# BluetoothBoard.net
KiCad netlist of a schematic drawn in EAGLE
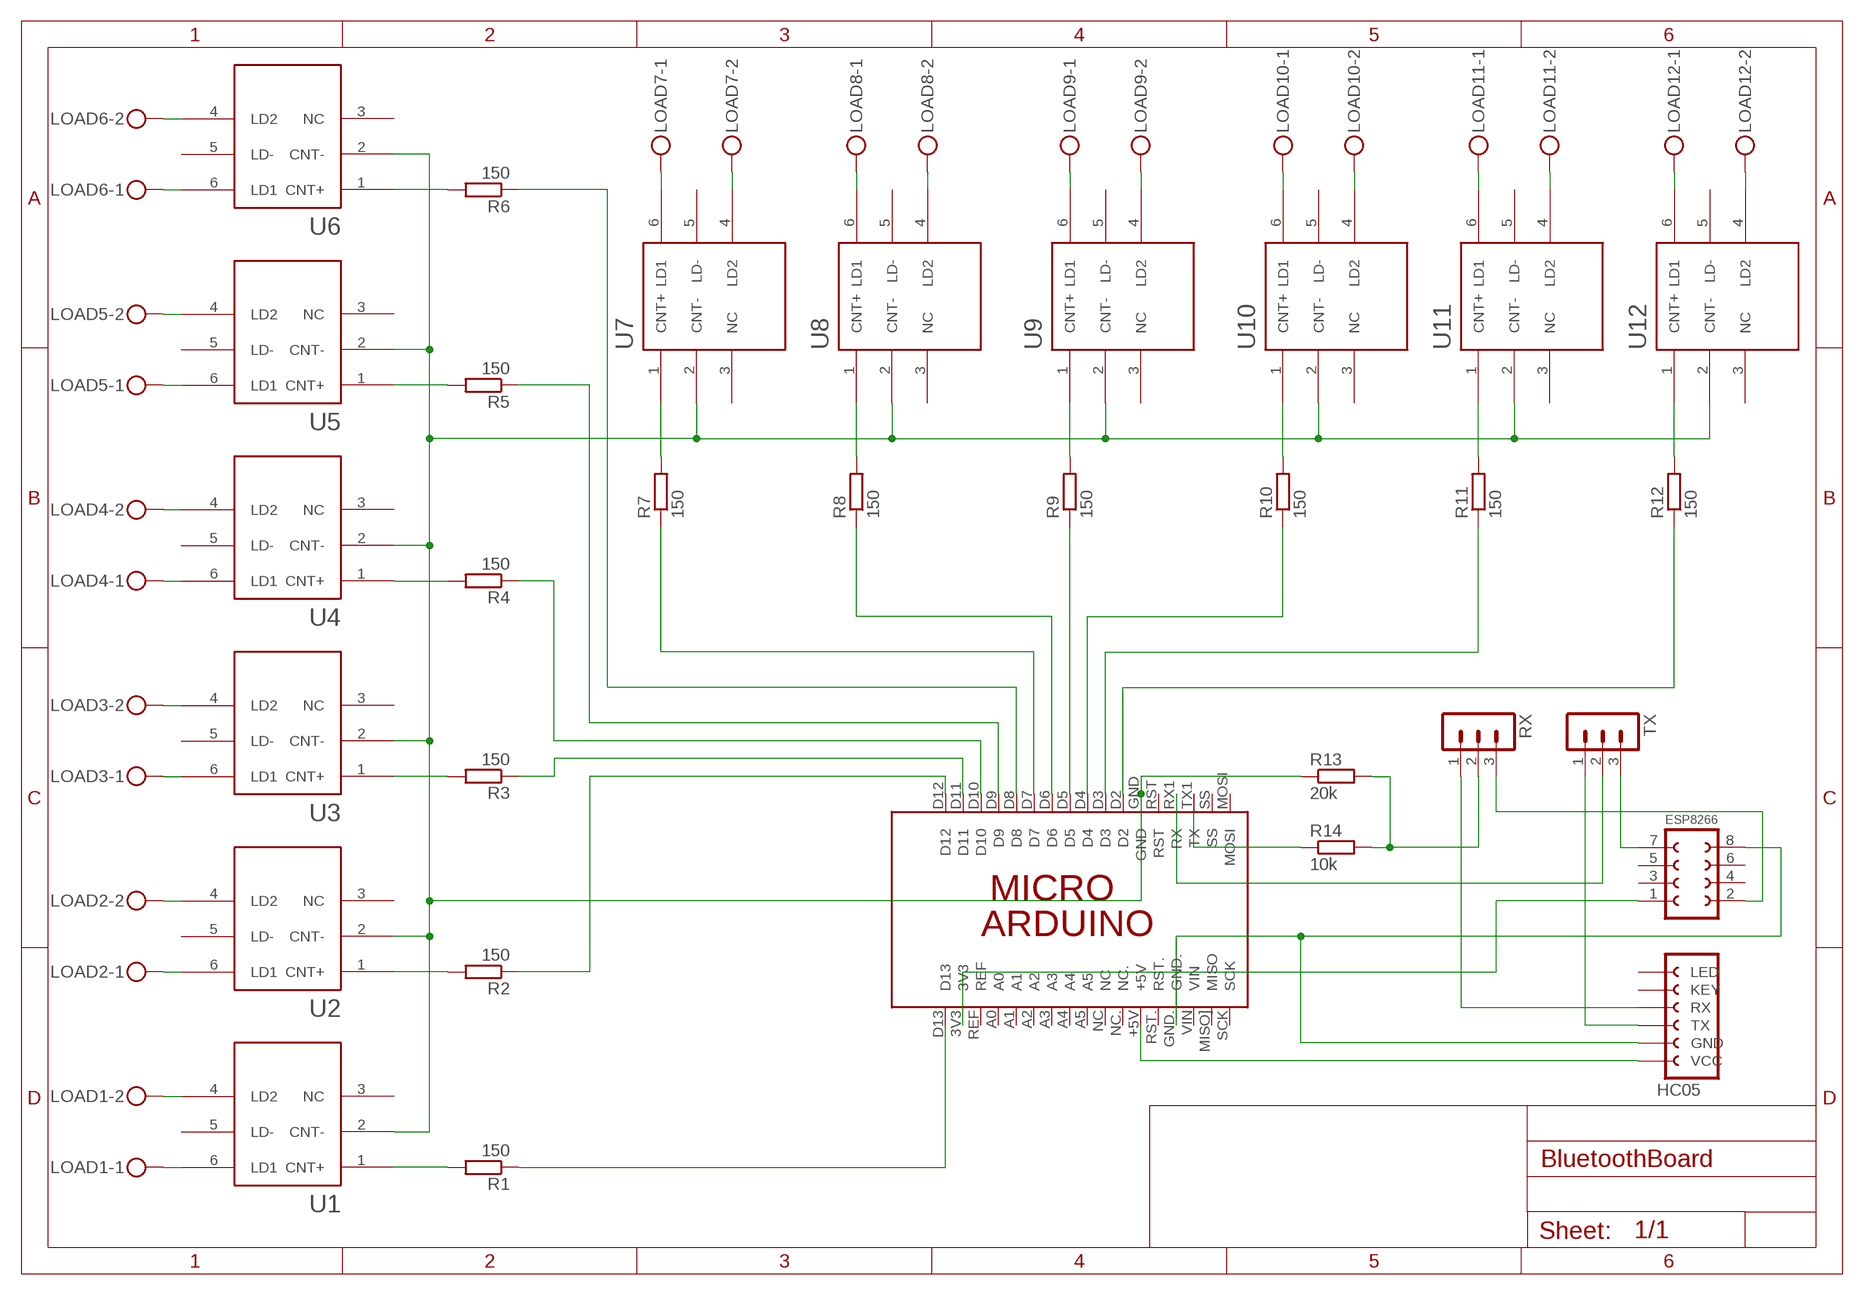
[diagram p0: schematic, sheet 1]

(export (version "E")
  (design (tool "Eeschema 10.0.6"))
  (components
    (comp (ref "ESP8266")
      (value "ESP8266")
      (footprint "eagle-import:ESP8266")
      (libsource (lib "eagle-import") (part "ESP8266"))
    )
    (comp (ref "HC05")
      (value "FE06-1")
      (footprint "eagle-import:FE06")
      (libsource (lib "eagle-import") (part "FE06-1"))
    )
    (comp (ref "LOAD1")
      (value "MKDSN1,5/2-5,08")
      (footprint "eagle-import:MKDSN1,5_2-5,08")
      (libsource (lib "eagle-import") (part "MKDSN1,5/2-5,08"))
    )
    (comp (ref "LOAD2")
      (value "MKDSN1,5/2-5,08")
      (footprint "eagle-import:MKDSN1,5_2-5,08")
      (libsource (lib "eagle-import") (part "MKDSN1,5/2-5,08"))
    )
    (comp (ref "LOAD3")
      (value "MKDSN1,5/2-5,08")
      (footprint "eagle-import:MKDSN1,5_2-5,08")
      (libsource (lib "eagle-import") (part "MKDSN1,5/2-5,08"))
    )
    (comp (ref "LOAD4")
      (value "MKDSN1,5/2-5,08")
      (footprint "eagle-import:MKDSN1,5_2-5,08")
      (libsource (lib "eagle-import") (part "MKDSN1,5/2-5,08"))
    )
    (comp (ref "LOAD5")
      (value "MKDSN1,5/2-5,08")
      (footprint "eagle-import:MKDSN1,5_2-5,08")
      (libsource (lib "eagle-import") (part "MKDSN1,5/2-5,08"))
    )
    (comp (ref "LOAD6")
      (value "MKDSN1,5/2-5,08")
      (footprint "eagle-import:MKDSN1,5_2-5,08")
      (libsource (lib "eagle-import") (part "MKDSN1,5/2-5,08"))
    )
    (comp (ref "LOAD7")
      (value "MKDSN1,5/2-5,08")
      (footprint "eagle-import:MKDSN1,5_2-5,08")
      (libsource (lib "eagle-import") (part "MKDSN1,5/2-5,08"))
    )
    (comp (ref "LOAD8")
      (value "MKDSN1,5/2-5,08")
      (footprint "eagle-import:MKDSN1,5_2-5,08")
      (libsource (lib "eagle-import") (part "MKDSN1,5/2-5,08"))
    )
    (comp (ref "LOAD9")
      (value "MKDSN1,5/2-5,08")
      (footprint "eagle-import:MKDSN1,5_2-5,08")
      (libsource (lib "eagle-import") (part "MKDSN1,5/2-5,08"))
    )
    (comp (ref "LOAD10")
      (value "MKDSN1,5/2-5,08")
      (footprint "eagle-import:MKDSN1,5_2-5,08")
      (libsource (lib "eagle-import") (part "MKDSN1,5/2-5,08"))
    )
    (comp (ref "LOAD11")
      (value "MKDSN1,5/2-5,08")
      (footprint "eagle-import:MKDSN1,5_2-5,08")
      (libsource (lib "eagle-import") (part "MKDSN1,5/2-5,08"))
    )
    (comp (ref "LOAD12")
      (value "MKDSN1,5/2-5,08")
      (footprint "eagle-import:MKDSN1,5_2-5,08")
      (libsource (lib "eagle-import") (part "MKDSN1,5/2-5,08"))
    )
    (comp (ref "R1")
      (value "150")
      (footprint "eagle-import:0207_7")
      (libsource (lib "eagle-import") (part "R-EU_0207/7"))
    )
    (comp (ref "R2")
      (value "150")
      (footprint "eagle-import:0207_7")
      (libsource (lib "eagle-import") (part "R-EU_0207/7"))
    )
    (comp (ref "R3")
      (value "150")
      (footprint "eagle-import:0207_7")
      (libsource (lib "eagle-import") (part "R-EU_0207/7"))
    )
    (comp (ref "R4")
      (value "150")
      (footprint "eagle-import:0207_7")
      (libsource (lib "eagle-import") (part "R-EU_0207/7"))
    )
    (comp (ref "R5")
      (value "150")
      (footprint "eagle-import:0207_7")
      (libsource (lib "eagle-import") (part "R-EU_0207/7"))
    )
    (comp (ref "R6")
      (value "150")
      (footprint "eagle-import:0207_7")
      (libsource (lib "eagle-import") (part "R-EU_0207/7"))
    )
    (comp (ref "R7")
      (value "150")
      (footprint "eagle-import:0207_7")
      (libsource (lib "eagle-import") (part "R-EU_0207/7"))
    )
    (comp (ref "R8")
      (value "150")
      (footprint "eagle-import:0207_7")
      (libsource (lib "eagle-import") (part "R-EU_0207/7"))
    )
    (comp (ref "R9")
      (value "150")
      (footprint "eagle-import:0207_7")
      (libsource (lib "eagle-import") (part "R-EU_0207/7"))
    )
    (comp (ref "R10")
      (value "150")
      (footprint "eagle-import:0207_7")
      (libsource (lib "eagle-import") (part "R-EU_0207/7"))
    )
    (comp (ref "R11")
      (value "150")
      (footprint "eagle-import:0207_7")
      (libsource (lib "eagle-import") (part "R-EU_0207/7"))
    )
    (comp (ref "R12")
      (value "150")
      (footprint "eagle-import:0207_7")
      (libsource (lib "eagle-import") (part "R-EU_0207/7"))
    )
    (comp (ref "R13")
      (value "20k")
      (footprint "eagle-import:0207_7")
      (libsource (lib "eagle-import") (part "R-EU_0207/7"))
    )
    (comp (ref "R14")
      (value "10k")
      (footprint "eagle-import:0207_7")
      (libsource (lib "eagle-import") (part "R-EU_0207/7"))
    )
    (comp (ref "RX")
      (value "MA03-1")
      (footprint "eagle-import:MA03-1")
      (libsource (lib "eagle-import") (part "MA03-1"))
    )
    (comp (ref "TX")
      (value "MA03-1")
      (footprint "eagle-import:MA03-1")
      (libsource (lib "eagle-import") (part "MA03-1"))
    )
    (comp (ref "U1")
      (value "LCA710")
      (footprint "eagle-import:DIL-06")
      (libsource (lib "eagle-import") (part "LCA710"))
    )
    (comp (ref "U2")
      (value "LCA710")
      (footprint "eagle-import:DIL-06")
      (libsource (lib "eagle-import") (part "LCA710"))
    )
    (comp (ref "U3")
      (value "LCA710")
      (footprint "eagle-import:DIL-06")
      (libsource (lib "eagle-import") (part "LCA710"))
    )
    (comp (ref "U4")
      (value "LCA710")
      (footprint "eagle-import:DIL-06")
      (libsource (lib "eagle-import") (part "LCA710"))
    )
    (comp (ref "U5")
      (value "LCA710")
      (footprint "eagle-import:DIL-06")
      (libsource (lib "eagle-import") (part "LCA710"))
    )
    (comp (ref "U6")
      (value "LCA710")
      (footprint "eagle-import:DIL-06")
      (libsource (lib "eagle-import") (part "LCA710"))
    )
    (comp (ref "U7")
      (value "LCA710")
      (footprint "eagle-import:DIL-06")
      (libsource (lib "eagle-import") (part "LCA710"))
    )
    (comp (ref "U8")
      (value "LCA710")
      (footprint "eagle-import:DIL-06")
      (libsource (lib "eagle-import") (part "LCA710"))
    )
    (comp (ref "U9")
      (value "LCA710")
      (footprint "eagle-import:DIL-06")
      (libsource (lib "eagle-import") (part "LCA710"))
    )
    (comp (ref "U10")
      (value "LCA710")
      (footprint "eagle-import:DIL-06")
      (libsource (lib "eagle-import") (part "LCA710"))
    )
    (comp (ref "U11")
      (value "LCA710")
      (footprint "eagle-import:DIL-06")
      (libsource (lib "eagle-import") (part "LCA710"))
    )
    (comp (ref "U12")
      (value "LCA710")
      (footprint "eagle-import:DIL-06")
      (libsource (lib "eagle-import") (part "LCA710"))
    )
    (comp (ref "UC")
      (value "ARDUINO_MICRO")
      (footprint "eagle-import:ARDUINO_MICRO")
      (libsource (lib "eagle-import") (part "ARDUINO_MICRO"))
    )
  )
  (nets
    (net (code "1") (name "Net-(ESP8266-Pad1)") (class "Default")
      (node (ref "ESP8266") (pin "1") (pinfunction "1_1") (pintype "passive"))
      (node (ref "UC") (pin "3V3") (pinfunction "3V3_3V3") (pintype "bidirectional"))
    )
    (net (code "2") (name "Net-(ESP8266-Pad2)") (class "Default")
      (node (ref "ESP8266") (pin "2") (pinfunction "2_2") (pintype "passive"))
      (node (ref "RX") (pin "3") (pinfunction "3_3") (pintype "passive"))
    )
    (net (code "3") (name "Net-(ESP8266-TX)") (class "Default")
      (node (ref "ESP8266") (pin "7") (pinfunction "TX_7") (pintype "passive"))
      (node (ref "TX") (pin "3") (pinfunction "3_3") (pintype "passive"))
    )
    (net (code "4") (name "Net-(HC05-GND)") (class "Default")
      (node (ref "ESP8266") (pin "8") (pinfunction "8_8") (pintype "passive"))
      (node (ref "HC05") (pin "5") (pinfunction "GND_5") (pintype "passive"))
      (node (ref "UC") (pin "GND.") (pinfunction "GND._GND.") (pintype "bidirectional"))
    )
    (net (code "5") (name "Net-(HC05-RX)") (class "Default")
      (node (ref "HC05") (pin "3") (pinfunction "RX_3") (pintype "passive"))
      (node (ref "RX") (pin "1") (pinfunction "1_1") (pintype "passive"))
    )
    (net (code "6") (name "Net-(HC05-TX)") (class "Default")
      (node (ref "HC05") (pin "4") (pinfunction "TX_4") (pintype "passive"))
      (node (ref "TX") (pin "1") (pinfunction "1_1") (pintype "passive"))
    )
    (net (code "7") (name "Net-(HC05-VCC)") (class "Default")
      (node (ref "HC05") (pin "6") (pinfunction "VCC_6") (pintype "passive"))
      (node (ref "UC") (pin "+5V") (pinfunction "+5V_+5V") (pintype "bidirectional"))
    )
    (net (code "8") (name "Net-(LOAD1A-KL)") (class "Default")
      (node (ref "LOAD1") (pin "1") (pinfunction "KL_1") (pintype "passive"))
      (node (ref "U1") (pin "6") (pinfunction "LD1_6") (pintype "passive"))
    )
    (net (code "9") (name "Net-(LOAD1B-KL)") (class "Default")
      (node (ref "LOAD1") (pin "2") (pinfunction "KL_2") (pintype "passive"))
      (node (ref "U1") (pin "4") (pinfunction "LD2_4") (pintype "passive"))
    )
    (net (code "10") (name "Net-(LOAD2A-KL)") (class "Default")
      (node (ref "LOAD2") (pin "1") (pinfunction "KL_1") (pintype "passive"))
      (node (ref "U2") (pin "6") (pinfunction "LD1_6") (pintype "passive"))
    )
    (net (code "11") (name "Net-(LOAD2B-KL)") (class "Default")
      (node (ref "LOAD2") (pin "2") (pinfunction "KL_2") (pintype "passive"))
      (node (ref "U2") (pin "4") (pinfunction "LD2_4") (pintype "passive"))
    )
    (net (code "12") (name "Net-(LOAD3A-KL)") (class "Default")
      (node (ref "LOAD3") (pin "1") (pinfunction "KL_1") (pintype "passive"))
      (node (ref "U3") (pin "6") (pinfunction "LD1_6") (pintype "passive"))
    )
    (net (code "13") (name "Net-(LOAD3B-KL)") (class "Default")
      (node (ref "LOAD3") (pin "2") (pinfunction "KL_2") (pintype "passive"))
      (node (ref "U3") (pin "4") (pinfunction "LD2_4") (pintype "passive"))
    )
    (net (code "14") (name "Net-(LOAD4A-KL)") (class "Default")
      (node (ref "LOAD4") (pin "1") (pinfunction "KL_1") (pintype "passive"))
      (node (ref "U4") (pin "6") (pinfunction "LD1_6") (pintype "passive"))
    )
    (net (code "15") (name "Net-(LOAD4B-KL)") (class "Default")
      (node (ref "LOAD4") (pin "2") (pinfunction "KL_2") (pintype "passive"))
      (node (ref "U4") (pin "4") (pinfunction "LD2_4") (pintype "passive"))
    )
    (net (code "16") (name "Net-(LOAD5A-KL)") (class "Default")
      (node (ref "LOAD5") (pin "1") (pinfunction "KL_1") (pintype "passive"))
      (node (ref "U5") (pin "6") (pinfunction "LD1_6") (pintype "passive"))
    )
    (net (code "17") (name "Net-(LOAD5B-KL)") (class "Default")
      (node (ref "LOAD5") (pin "2") (pinfunction "KL_2") (pintype "passive"))
      (node (ref "U5") (pin "4") (pinfunction "LD2_4") (pintype "passive"))
    )
    (net (code "18") (name "Net-(LOAD6A-KL)") (class "Default")
      (node (ref "LOAD6") (pin "1") (pinfunction "KL_1") (pintype "passive"))
      (node (ref "U6") (pin "6") (pinfunction "LD1_6") (pintype "passive"))
    )
    (net (code "19") (name "Net-(LOAD6B-KL)") (class "Default")
      (node (ref "LOAD6") (pin "2") (pinfunction "KL_2") (pintype "passive"))
      (node (ref "U6") (pin "4") (pinfunction "LD2_4") (pintype "passive"))
    )
    (net (code "20") (name "Net-(LOAD7A-KL)") (class "Default")
      (node (ref "LOAD7") (pin "1") (pinfunction "KL_1") (pintype "passive"))
      (node (ref "U7") (pin "6") (pinfunction "LD1_6") (pintype "passive"))
    )
    (net (code "21") (name "Net-(LOAD7B-KL)") (class "Default")
      (node (ref "LOAD7") (pin "2") (pinfunction "KL_2") (pintype "passive"))
      (node (ref "U7") (pin "4") (pinfunction "LD2_4") (pintype "passive"))
    )
    (net (code "22") (name "Net-(LOAD8A-KL)") (class "Default")
      (node (ref "LOAD8") (pin "1") (pinfunction "KL_1") (pintype "passive"))
      (node (ref "U8") (pin "6") (pinfunction "LD1_6") (pintype "passive"))
    )
    (net (code "23") (name "Net-(LOAD8B-KL)") (class "Default")
      (node (ref "LOAD8") (pin "2") (pinfunction "KL_2") (pintype "passive"))
      (node (ref "U8") (pin "4") (pinfunction "LD2_4") (pintype "passive"))
    )
    (net (code "24") (name "Net-(LOAD9A-KL)") (class "Default")
      (node (ref "LOAD9") (pin "1") (pinfunction "KL_1") (pintype "passive"))
      (node (ref "U9") (pin "6") (pinfunction "LD1_6") (pintype "passive"))
    )
    (net (code "25") (name "Net-(LOAD9B-KL)") (class "Default")
      (node (ref "LOAD9") (pin "2") (pinfunction "KL_2") (pintype "passive"))
      (node (ref "U9") (pin "4") (pinfunction "LD2_4") (pintype "passive"))
    )
    (net (code "26") (name "Net-(LOAD10A-KL)") (class "Default")
      (node (ref "LOAD10") (pin "1") (pinfunction "KL_1") (pintype "passive"))
      (node (ref "U10") (pin "6") (pinfunction "LD1_6") (pintype "passive"))
    )
    (net (code "27") (name "Net-(LOAD10B-KL)") (class "Default")
      (node (ref "LOAD10") (pin "2") (pinfunction "KL_2") (pintype "passive"))
      (node (ref "U10") (pin "4") (pinfunction "LD2_4") (pintype "passive"))
    )
    (net (code "28") (name "Net-(LOAD11A-KL)") (class "Default")
      (node (ref "LOAD11") (pin "1") (pinfunction "KL_1") (pintype "passive"))
      (node (ref "U11") (pin "6") (pinfunction "LD1_6") (pintype "passive"))
    )
    (net (code "29") (name "Net-(LOAD11B-KL)") (class "Default")
      (node (ref "LOAD11") (pin "2") (pinfunction "KL_2") (pintype "passive"))
      (node (ref "U11") (pin "4") (pinfunction "LD2_4") (pintype "passive"))
    )
    (net (code "30") (name "Net-(LOAD12A-KL)") (class "Default")
      (node (ref "LOAD12") (pin "1") (pinfunction "KL_1") (pintype "passive"))
      (node (ref "U12") (pin "6") (pinfunction "LD1_6") (pintype "passive"))
    )
    (net (code "31") (name "Net-(LOAD12B-KL)") (class "Default")
      (node (ref "LOAD12") (pin "2") (pinfunction "KL_2") (pintype "passive"))
      (node (ref "U12") (pin "4") (pinfunction "LD2_4") (pintype "passive"))
    )
    (net (code "32") (name "Net-(R1-Pad1)") (class "Default")
      (node (ref "R1") (pin "1") (pinfunction "1_1") (pintype "passive"))
      (node (ref "UC") (pin "D13") (pinfunction "D13_D13") (pintype "bidirectional"))
    )
    (net (code "33") (name "Net-(R2-Pad1)") (class "Default")
      (node (ref "R2") (pin "1") (pinfunction "1_1") (pintype "passive"))
      (node (ref "UC") (pin "D12") (pinfunction "D12_D12") (pintype "bidirectional"))
    )
    (net (code "34") (name "Net-(R3-Pad1)") (class "Default")
      (node (ref "R3") (pin "1") (pinfunction "1_1") (pintype "passive"))
      (node (ref "UC") (pin "D11") (pinfunction "D11_D11") (pintype "bidirectional"))
    )
    (net (code "35") (name "Net-(R4-Pad1)") (class "Default")
      (node (ref "R4") (pin "1") (pinfunction "1_1") (pintype "passive"))
      (node (ref "UC") (pin "D10") (pinfunction "D10_D10") (pintype "bidirectional"))
    )
    (net (code "36") (name "Net-(R5-Pad1)") (class "Default")
      (node (ref "R5") (pin "1") (pinfunction "1_1") (pintype "passive"))
      (node (ref "UC") (pin "D9") (pinfunction "D9_D9") (pintype "bidirectional"))
    )
    (net (code "37") (name "Net-(R6-Pad1)") (class "Default")
      (node (ref "R6") (pin "1") (pinfunction "1_1") (pintype "passive"))
      (node (ref "UC") (pin "D8") (pinfunction "D8_D8") (pintype "bidirectional"))
    )
    (net (code "38") (name "Net-(R7-Pad1)") (class "Default")
      (node (ref "R7") (pin "1") (pinfunction "1_1") (pintype "passive"))
      (node (ref "UC") (pin "D7") (pinfunction "D7_D7") (pintype "bidirectional"))
    )
    (net (code "39") (name "Net-(R8-Pad1)") (class "Default")
      (node (ref "R8") (pin "1") (pinfunction "1_1") (pintype "passive"))
      (node (ref "UC") (pin "D6") (pinfunction "D6_D6") (pintype "bidirectional"))
    )
    (net (code "40") (name "Net-(R9-Pad1)") (class "Default")
      (node (ref "R9") (pin "1") (pinfunction "1_1") (pintype "passive"))
      (node (ref "UC") (pin "D5") (pinfunction "D5_D5") (pintype "bidirectional"))
    )
    (net (code "41") (name "Net-(R10-Pad1)") (class "Default")
      (node (ref "R10") (pin "1") (pinfunction "1_1") (pintype "passive"))
      (node (ref "UC") (pin "D4") (pinfunction "D4_D4") (pintype "bidirectional"))
    )
    (net (code "42") (name "Net-(R11-Pad1)") (class "Default")
      (node (ref "R11") (pin "1") (pinfunction "1_1") (pintype "passive"))
      (node (ref "UC") (pin "D3") (pinfunction "D3_D3") (pintype "bidirectional"))
    )
    (net (code "43") (name "Net-(R12-Pad1)") (class "Default")
      (node (ref "R12") (pin "1") (pinfunction "1_1") (pintype "passive"))
      (node (ref "UC") (pin "D2") (pinfunction "D2_D2") (pintype "bidirectional"))
    )
    (net (code "44") (name "Net-(R13-Pad2)") (class "Default")
      (node (ref "R13") (pin "2") (pinfunction "2_2") (pintype "passive"))
      (node (ref "R14") (pin "2") (pinfunction "2_2") (pintype "passive"))
      (node (ref "RX") (pin "2") (pinfunction "2_2") (pintype "passive"))
    )
    (net (code "45") (name "Net-(U1-CNT+)") (class "Default")
      (node (ref "R1") (pin "2") (pinfunction "2_2") (pintype "passive"))
      (node (ref "U1") (pin "1") (pinfunction "CNT+_1") (pintype "passive"))
    )
    (net (code "46") (name "Net-(U1-CNT-)") (class "Default")
      (node (ref "R13") (pin "1") (pinfunction "1_1") (pintype "passive"))
      (node (ref "U1") (pin "2") (pinfunction "CNT-_2") (pintype "passive"))
      (node (ref "U10") (pin "2") (pinfunction "CNT-_2") (pintype "passive"))
      (node (ref "U11") (pin "2") (pinfunction "CNT-_2") (pintype "passive"))
      (node (ref "U12") (pin "2") (pinfunction "CNT-_2") (pintype "passive"))
      (node (ref "U2") (pin "2") (pinfunction "CNT-_2") (pintype "passive"))
      (node (ref "U3") (pin "2") (pinfunction "CNT-_2") (pintype "passive"))
      (node (ref "U4") (pin "2") (pinfunction "CNT-_2") (pintype "passive"))
      (node (ref "U5") (pin "2") (pinfunction "CNT-_2") (pintype "passive"))
      (node (ref "U6") (pin "2") (pinfunction "CNT-_2") (pintype "passive"))
      (node (ref "U7") (pin "2") (pinfunction "CNT-_2") (pintype "passive"))
      (node (ref "U8") (pin "2") (pinfunction "CNT-_2") (pintype "passive"))
      (node (ref "U9") (pin "2") (pinfunction "CNT-_2") (pintype "passive"))
      (node (ref "UC") (pin "GND") (pinfunction "GND_GND") (pintype "bidirectional"))
    )
    (net (code "47") (name "Net-(U2-CNT+)") (class "Default")
      (node (ref "R2") (pin "2") (pinfunction "2_2") (pintype "passive"))
      (node (ref "U2") (pin "1") (pinfunction "CNT+_1") (pintype "passive"))
    )
    (net (code "48") (name "Net-(U3-CNT+)") (class "Default")
      (node (ref "R3") (pin "2") (pinfunction "2_2") (pintype "passive"))
      (node (ref "U3") (pin "1") (pinfunction "CNT+_1") (pintype "passive"))
    )
    (net (code "49") (name "Net-(U4-CNT+)") (class "Default")
      (node (ref "R4") (pin "2") (pinfunction "2_2") (pintype "passive"))
      (node (ref "U4") (pin "1") (pinfunction "CNT+_1") (pintype "passive"))
    )
    (net (code "50") (name "Net-(U5-CNT+)") (class "Default")
      (node (ref "R5") (pin "2") (pinfunction "2_2") (pintype "passive"))
      (node (ref "U5") (pin "1") (pinfunction "CNT+_1") (pintype "passive"))
    )
    (net (code "51") (name "Net-(U6-CNT+)") (class "Default")
      (node (ref "R6") (pin "2") (pinfunction "2_2") (pintype "passive"))
      (node (ref "U6") (pin "1") (pinfunction "CNT+_1") (pintype "passive"))
    )
    (net (code "52") (name "Net-(U7-CNT+)") (class "Default")
      (node (ref "R7") (pin "2") (pinfunction "2_2") (pintype "passive"))
      (node (ref "U7") (pin "1") (pinfunction "CNT+_1") (pintype "passive"))
    )
    (net (code "53") (name "Net-(U8-CNT+)") (class "Default")
      (node (ref "R8") (pin "2") (pinfunction "2_2") (pintype "passive"))
      (node (ref "U8") (pin "1") (pinfunction "CNT+_1") (pintype "passive"))
    )
    (net (code "54") (name "Net-(U9-CNT+)") (class "Default")
      (node (ref "R9") (pin "2") (pinfunction "2_2") (pintype "passive"))
      (node (ref "U9") (pin "1") (pinfunction "CNT+_1") (pintype "passive"))
    )
    (net (code "55") (name "Net-(U10-CNT+)") (class "Default")
      (node (ref "R10") (pin "2") (pinfunction "2_2") (pintype "passive"))
      (node (ref "U10") (pin "1") (pinfunction "CNT+_1") (pintype "passive"))
    )
    (net (code "56") (name "Net-(U11-CNT+)") (class "Default")
      (node (ref "R11") (pin "2") (pinfunction "2_2") (pintype "passive"))
      (node (ref "U11") (pin "1") (pinfunction "CNT+_1") (pintype "passive"))
    )
    (net (code "57") (name "Net-(U12-CNT+)") (class "Default")
      (node (ref "R12") (pin "2") (pinfunction "2_2") (pintype "passive"))
      (node (ref "U12") (pin "1") (pinfunction "CNT+_1") (pintype "passive"))
    )
    (net (code "58") (name "Net-(UC-RX)") (class "Default")
      (node (ref "TX") (pin "2") (pinfunction "2_2") (pintype "passive"))
      (node (ref "UC") (pin "RX1") (pinfunction "RX_RX1") (pintype "bidirectional"))
    )
    (net (code "59") (name "Net-(UC-TX)") (class "Default")
      (node (ref "R14") (pin "1") (pinfunction "1_1") (pintype "passive"))
      (node (ref "UC") (pin "TX1") (pinfunction "TX_TX1") (pintype "bidirectional"))
    )
    (net (code "60") (name "unconnected-(ESP8266-Pad3)") (class "Default")
      (node (ref "ESP8266") (pin "3") (pinfunction "3_3") (pintype "passive"))
    )
    (net (code "61") (name "unconnected-(ESP8266-Pad4)") (class "Default")
      (node (ref "ESP8266") (pin "4") (pinfunction "4_4") (pintype "passive"))
    )
    (net (code "62") (name "unconnected-(ESP8266-Pad5)") (class "Default")
      (node (ref "ESP8266") (pin "5") (pinfunction "5_5") (pintype "passive"))
    )
    (net (code "63") (name "unconnected-(ESP8266-Pad6)") (class "Default")
      (node (ref "ESP8266") (pin "6") (pinfunction "6_6") (pintype "passive"))
    )
    (net (code "64") (name "unconnected-(HC05-KEY-Pad2)") (class "Default")
      (node (ref "HC05") (pin "2") (pinfunction "KEY_2") (pintype "passive"))
    )
    (net (code "65") (name "unconnected-(HC05-LED-Pad1)") (class "Default")
      (node (ref "HC05") (pin "1") (pinfunction "LED_1") (pintype "passive"))
    )
    (net (code "66") (name "unconnected-(U1-LD--Pad5)") (class "Default")
      (node (ref "U1") (pin "5") (pinfunction "LD-_5") (pintype "passive"))
    )
    (net (code "67") (name "unconnected-(U1-NC-Pad3)") (class "Default")
      (node (ref "U1") (pin "3") (pinfunction "NC_3") (pintype "passive"))
    )
    (net (code "68") (name "unconnected-(U2-LD--Pad5)") (class "Default")
      (node (ref "U2") (pin "5") (pinfunction "LD-_5") (pintype "passive"))
    )
    (net (code "69") (name "unconnected-(U2-NC-Pad3)") (class "Default")
      (node (ref "U2") (pin "3") (pinfunction "NC_3") (pintype "passive"))
    )
    (net (code "70") (name "unconnected-(U3-LD--Pad5)") (class "Default")
      (node (ref "U3") (pin "5") (pinfunction "LD-_5") (pintype "passive"))
    )
    (net (code "71") (name "unconnected-(U3-NC-Pad3)") (class "Default")
      (node (ref "U3") (pin "3") (pinfunction "NC_3") (pintype "passive"))
    )
    (net (code "72") (name "unconnected-(U4-LD--Pad5)") (class "Default")
      (node (ref "U4") (pin "5") (pinfunction "LD-_5") (pintype "passive"))
    )
    (net (code "73") (name "unconnected-(U4-NC-Pad3)") (class "Default")
      (node (ref "U4") (pin "3") (pinfunction "NC_3") (pintype "passive"))
    )
    (net (code "74") (name "unconnected-(U5-LD--Pad5)") (class "Default")
      (node (ref "U5") (pin "5") (pinfunction "LD-_5") (pintype "passive"))
    )
    (net (code "75") (name "unconnected-(U5-NC-Pad3)") (class "Default")
      (node (ref "U5") (pin "3") (pinfunction "NC_3") (pintype "passive"))
    )
    (net (code "76") (name "unconnected-(U6-LD--Pad5)") (class "Default")
      (node (ref "U6") (pin "5") (pinfunction "LD-_5") (pintype "passive"))
    )
    (net (code "77") (name "unconnected-(U6-NC-Pad3)") (class "Default")
      (node (ref "U6") (pin "3") (pinfunction "NC_3") (pintype "passive"))
    )
    (net (code "78") (name "unconnected-(U7-LD--Pad5)") (class "Default")
      (node (ref "U7") (pin "5") (pinfunction "LD-_5") (pintype "passive"))
    )
    (net (code "79") (name "unconnected-(U7-NC-Pad3)") (class "Default")
      (node (ref "U7") (pin "3") (pinfunction "NC_3") (pintype "passive"))
    )
    (net (code "80") (name "unconnected-(U8-LD--Pad5)") (class "Default")
      (node (ref "U8") (pin "5") (pinfunction "LD-_5") (pintype "passive"))
    )
    (net (code "81") (name "unconnected-(U8-NC-Pad3)") (class "Default")
      (node (ref "U8") (pin "3") (pinfunction "NC_3") (pintype "passive"))
    )
    (net (code "82") (name "unconnected-(U9-LD--Pad5)") (class "Default")
      (node (ref "U9") (pin "5") (pinfunction "LD-_5") (pintype "passive"))
    )
    (net (code "83") (name "unconnected-(U9-NC-Pad3)") (class "Default")
      (node (ref "U9") (pin "3") (pinfunction "NC_3") (pintype "passive"))
    )
    (net (code "84") (name "unconnected-(U10-LD--Pad5)") (class "Default")
      (node (ref "U10") (pin "5") (pinfunction "LD-_5") (pintype "passive"))
    )
    (net (code "85") (name "unconnected-(U10-NC-Pad3)") (class "Default")
      (node (ref "U10") (pin "3") (pinfunction "NC_3") (pintype "passive"))
    )
    (net (code "86") (name "unconnected-(U11-LD--Pad5)") (class "Default")
      (node (ref "U11") (pin "5") (pinfunction "LD-_5") (pintype "passive"))
    )
    (net (code "87") (name "unconnected-(U11-NC-Pad3)") (class "Default")
      (node (ref "U11") (pin "3") (pinfunction "NC_3") (pintype "passive"))
    )
    (net (code "88") (name "unconnected-(U12-LD--Pad5)") (class "Default")
      (node (ref "U12") (pin "5") (pinfunction "LD-_5") (pintype "passive"))
    )
    (net (code "89") (name "unconnected-(U12-NC-Pad3)") (class "Default")
      (node (ref "U12") (pin "3") (pinfunction "NC_3") (pintype "passive"))
    )
    (net (code "90") (name "unconnected-(UC-MISO-PadMISO])") (class "Default")
      (node (ref "UC") (pin "MISO]") (pinfunction "MISO_MISO]") (pintype "bidirectional"))
    )
    (net (code "91") (name "unconnected-(UC-PadA0)") (class "Default")
      (node (ref "UC") (pin "A0") (pinfunction "A0_A0") (pintype "bidirectional"))
    )
    (net (code "92") (name "unconnected-(UC-PadA1)") (class "Default")
      (node (ref "UC") (pin "A1") (pinfunction "A1_A1") (pintype "bidirectional"))
    )
    (net (code "93") (name "unconnected-(UC-PadA2)") (class "Default")
      (node (ref "UC") (pin "A2") (pinfunction "A2_A2") (pintype "bidirectional"))
    )
    (net (code "94") (name "unconnected-(UC-PadA3)") (class "Default")
      (node (ref "UC") (pin "A3") (pinfunction "A3_A3") (pintype "bidirectional"))
    )
    (net (code "95") (name "unconnected-(UC-PadA4)") (class "Default")
      (node (ref "UC") (pin "A4") (pinfunction "A4_A4") (pintype "bidirectional"))
    )
    (net (code "96") (name "unconnected-(UC-PadA5)") (class "Default")
      (node (ref "UC") (pin "A5") (pinfunction "A5_A5") (pintype "bidirectional"))
    )
    (net (code "97") (name "unconnected-(UC-PadMOSI)") (class "Default")
      (node (ref "UC") (pin "MOSI") (pinfunction "MOSI_MOSI") (pintype "bidirectional"))
    )
    (net (code "98") (name "unconnected-(UC-PadNC)") (class "Default")
      (node (ref "UC") (pin "NC") (pinfunction "NC_NC") (pintype "bidirectional"))
    )
    (net (code "99") (name "unconnected-(UC-PadNC.)") (class "Default")
      (node (ref "UC") (pin "NC.") (pinfunction "NC._NC.") (pintype "bidirectional"))
    )
    (net (code "100") (name "unconnected-(UC-PadREF)") (class "Default")
      (node (ref "UC") (pin "REF") (pinfunction "REF_REF") (pintype "bidirectional"))
    )
    (net (code "101") (name "unconnected-(UC-PadRST)") (class "Default")
      (node (ref "UC") (pin "RST") (pinfunction "RST_RST") (pintype "bidirectional"))
    )
    (net (code "102") (name "unconnected-(UC-PadRST.)") (class "Default")
      (node (ref "UC") (pin "RST.") (pinfunction "RST._RST.") (pintype "bidirectional"))
    )
    (net (code "103") (name "unconnected-(UC-PadSCK)") (class "Default")
      (node (ref "UC") (pin "SCK") (pinfunction "SCK_SCK") (pintype "bidirectional"))
    )
    (net (code "104") (name "unconnected-(UC-PadSS)") (class "Default")
      (node (ref "UC") (pin "SS") (pinfunction "SS_SS") (pintype "bidirectional"))
    )
    (net (code "105") (name "unconnected-(UC-PadVIN)") (class "Default")
      (node (ref "UC") (pin "VIN") (pinfunction "VIN_VIN") (pintype "bidirectional"))
    )
  )
)
